# RGBW_DirectControl_Eagle740.net
KiCad netlist of a schematic drawn in EAGLE
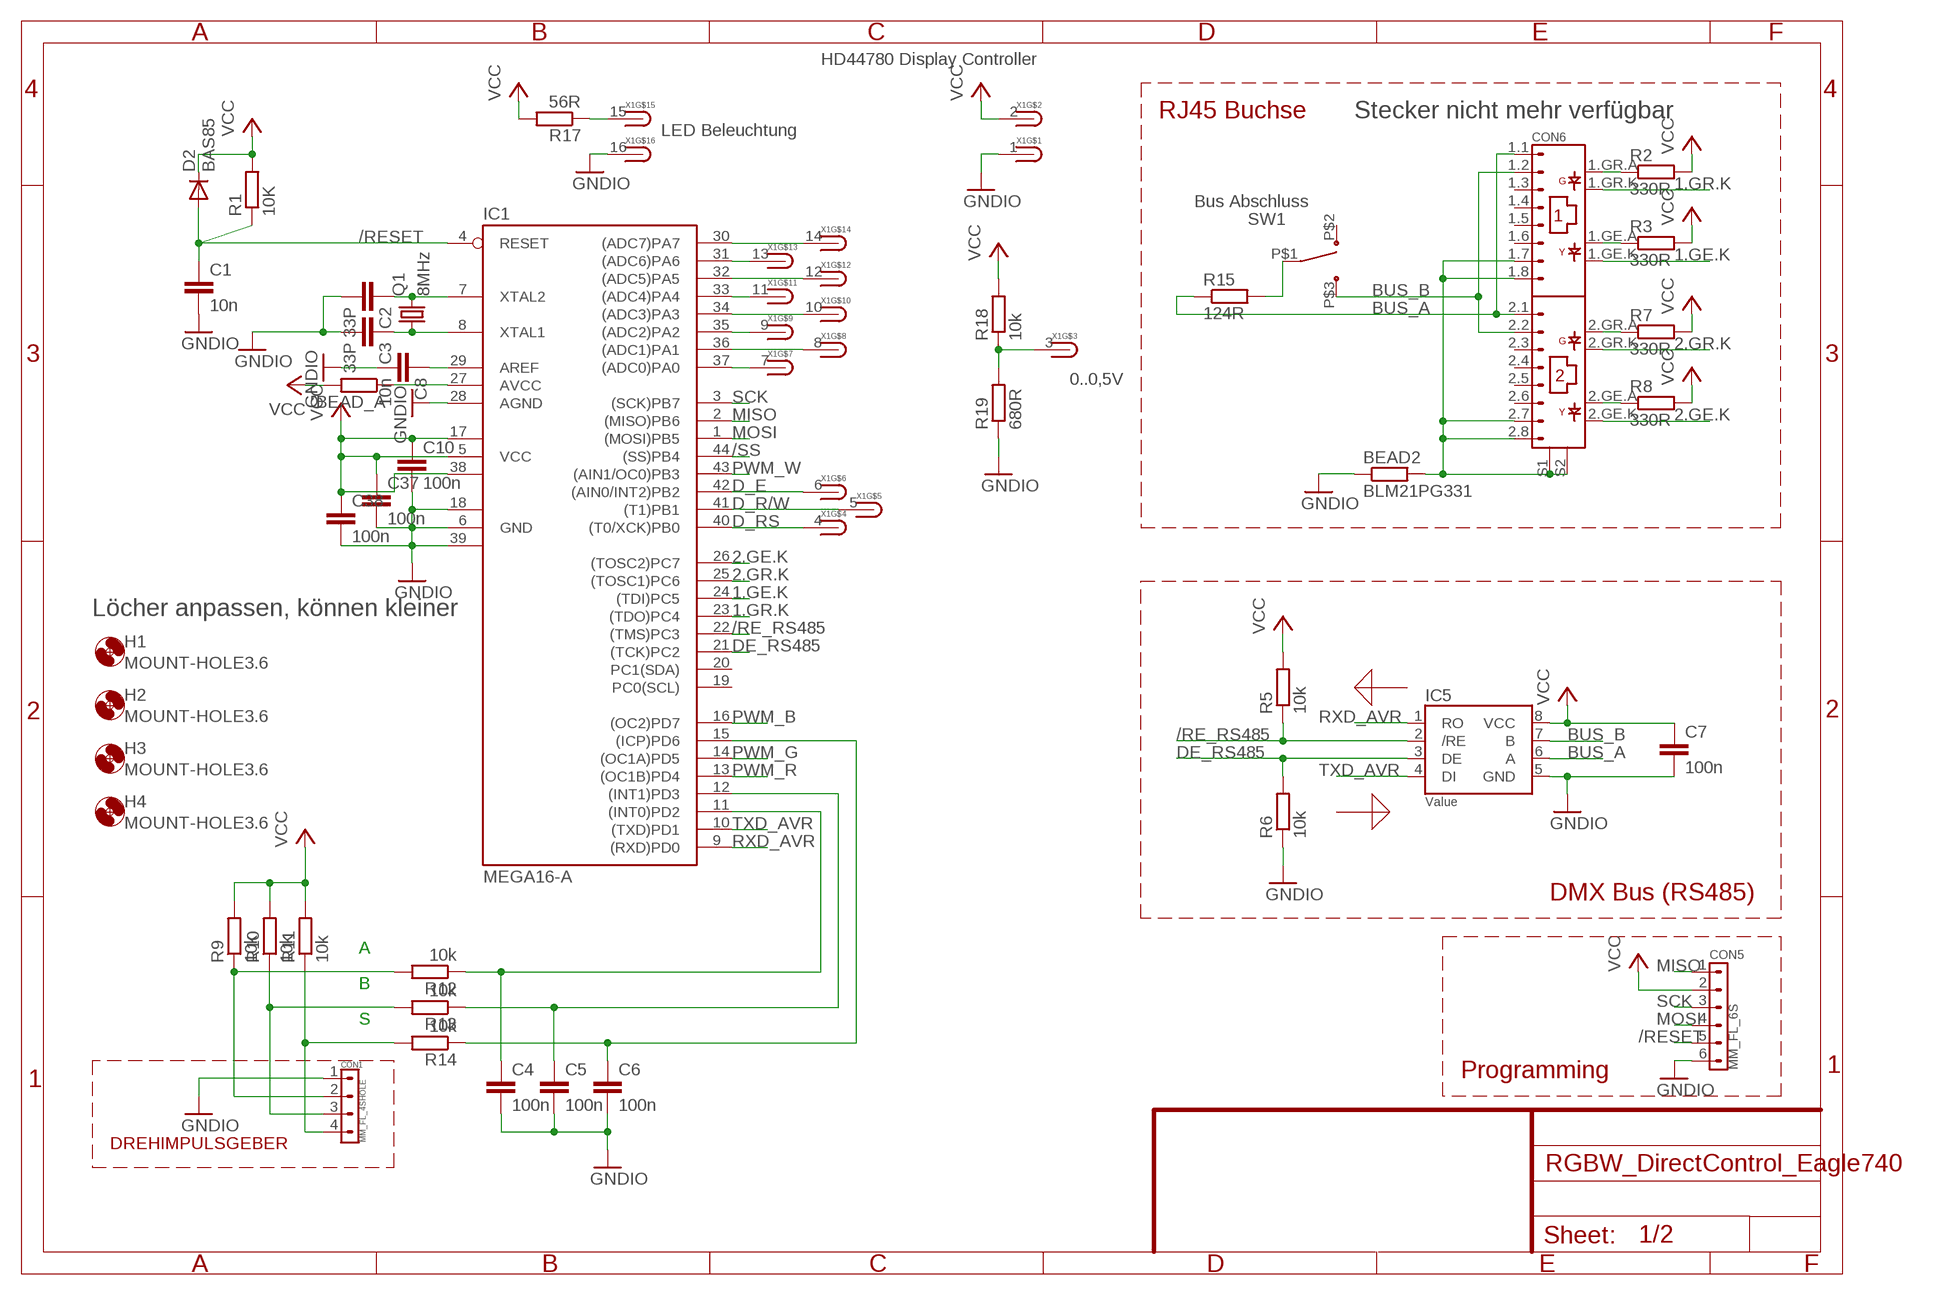
[diagram p0: schematic, sheet 1]
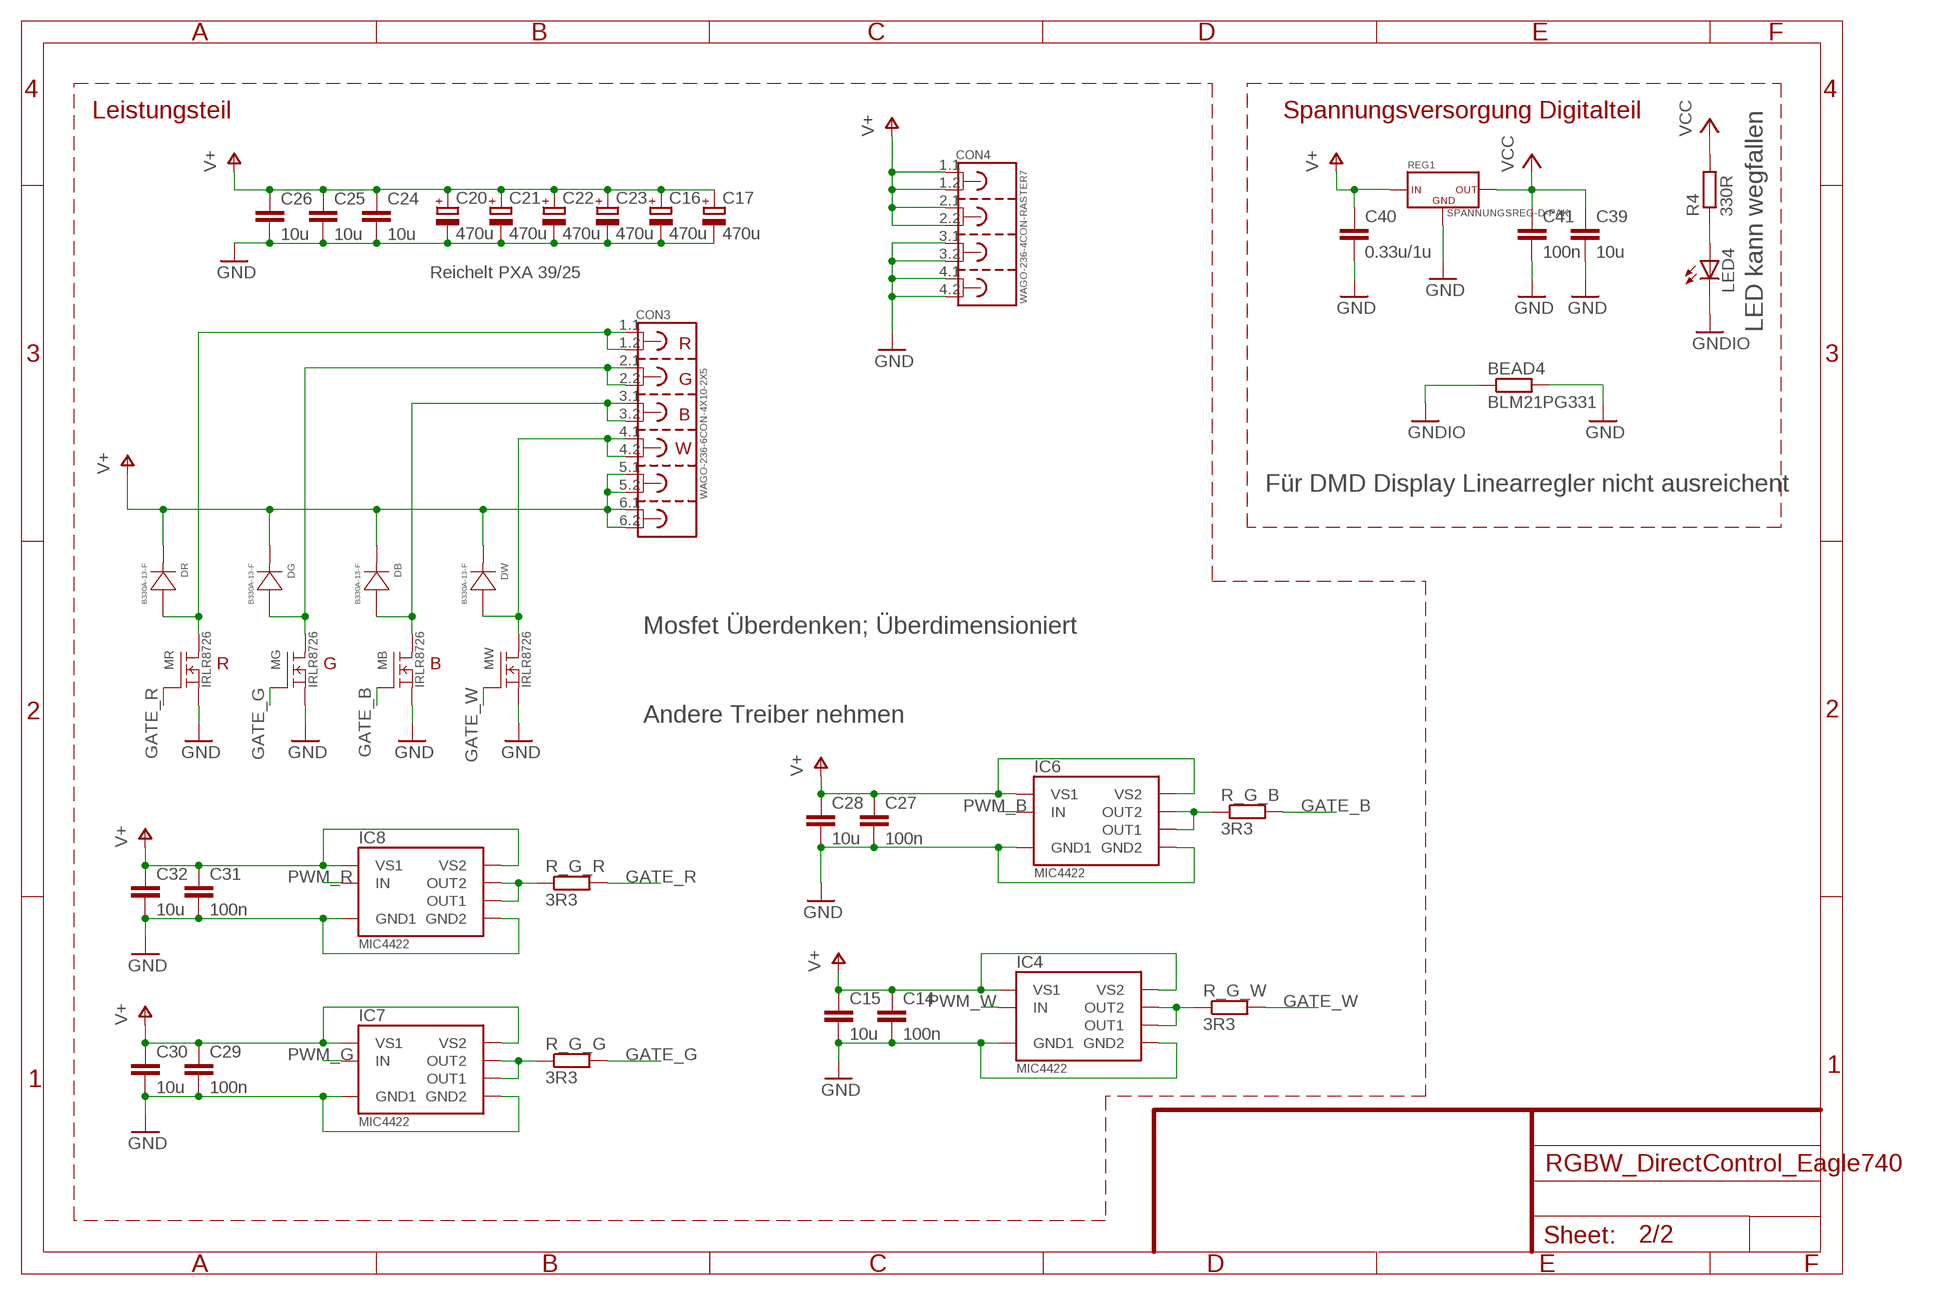
[diagram p1: schematic, sheet 2]

(export (version "E")
  (design (tool "Eeschema 10.0.6"))
  (components
    (comp (ref "BEAD2")
      (value "BLM21PG331")
      (footprint "eagle-import:R0805")
      (libsource (lib "eagle-import") (part "R-EU_R0805"))
    )
    (comp (ref "BEAD_A")
      (value "R-EU_R0805")
      (footprint "eagle-import:R0805")
      (libsource (lib "eagle-import") (part "R-EU_R0805"))
    )
    (comp (ref "C1")
      (value "10n")
      (footprint "eagle-import:C0805")
      (libsource (lib "eagle-import") (part "C-EUC0805"))
    )
    (comp (ref "C2")
      (value "33P")
      (footprint "eagle-import:C0805")
      (libsource (lib "eagle-import") (part "C-EUC0805"))
    )
    (comp (ref "C3")
      (value "33P")
      (footprint "eagle-import:C0805")
      (libsource (lib "eagle-import") (part "C-EUC0805"))
    )
    (comp (ref "C4")
      (value "100n")
      (footprint "eagle-import:C0805")
      (libsource (lib "eagle-import") (part "C-EUC0805"))
    )
    (comp (ref "C5")
      (value "100n")
      (footprint "eagle-import:C0805")
      (libsource (lib "eagle-import") (part "C-EUC0805"))
    )
    (comp (ref "C6")
      (value "100n")
      (footprint "eagle-import:C0805")
      (libsource (lib "eagle-import") (part "C-EUC0805"))
    )
    (comp (ref "C7")
      (value "100n")
      (footprint "eagle-import:C0805")
      (libsource (lib "eagle-import") (part "C-EUC0805"))
    )
    (comp (ref "C8")
      (value "10n")
      (footprint "eagle-import:C0805")
      (libsource (lib "eagle-import") (part "C-EUC0805"))
    )
    (comp (ref "C10")
      (value "100n")
      (footprint "eagle-import:C0805")
      (libsource (lib "eagle-import") (part "C-EUC0805"))
    )
    (comp (ref "C37")
      (value "100n")
      (footprint "eagle-import:C0805")
      (libsource (lib "eagle-import") (part "C-EUC0805"))
    )
    (comp (ref "C38")
      (value "100n")
      (footprint "eagle-import:C0805")
      (libsource (lib "eagle-import") (part "C-EUC0805"))
    )
    (comp (ref "CON1")
      (value "MM_FL_4SHOLE")
      (footprint "eagle-import:MM_FL_4G")
      (libsource (lib "eagle-import") (part "MM_FL_4SHOLE"))
    )
    (comp (ref "CON5")
      (value "MM_FL_6S")
      (footprint "eagle-import:MM_FL_6G")
      (libsource (lib "eagle-import") (part "MM_FL_6STH"))
    )
    (comp (ref "CON6")
      (value "RJ45_2ER_LED")
      (footprint "eagle-import:RJ45_2ER_LED")
      (libsource (lib "eagle-import") (part "RJ45_2ER_LED"))
    )
    (comp (ref "D2")
      (value "BAS85")
      (footprint "eagle-import:SOD80C")
      (libsource (lib "eagle-import") (part "DIODE-SOD80C"))
    )
    (comp (ref "H1")
      (value "MOUNT-HOLE3.6")
      (footprint "eagle-import:3,6")
      (libsource (lib "eagle-import") (part "MOUNT-HOLE3.6"))
    )
    (comp (ref "H2")
      (value "MOUNT-HOLE3.6")
      (footprint "eagle-import:3,6")
      (libsource (lib "eagle-import") (part "MOUNT-HOLE3.6"))
    )
    (comp (ref "H3")
      (value "MOUNT-HOLE3.6")
      (footprint "eagle-import:3,6")
      (libsource (lib "eagle-import") (part "MOUNT-HOLE3.6"))
    )
    (comp (ref "H4")
      (value "MOUNT-HOLE3.6")
      (footprint "eagle-import:3,6")
      (libsource (lib "eagle-import") (part "MOUNT-HOLE3.6"))
    )
    (comp (ref "IC1")
      (value "MEGA16-A")
      (footprint "eagle-import:TQFP44")
      (libsource (lib "eagle-import") (part "MEGA16-A"))
    )
    (comp (ref "IC5")
      (value "LT1785")
      (footprint "eagle-import:SO08")
      (libsource (lib "eagle-import") (part "LT1785"))
    )
    (comp (ref "Q1")
      (value "8MHz")
      (footprint "eagle-import:HC49_S")
      (libsource (lib "eagle-import") (part "CRYTALHC49S"))
    )
    (comp (ref "R1")
      (value "10K")
      (footprint "eagle-import:R0805")
      (libsource (lib "eagle-import") (part "R-EU_R0805"))
    )
    (comp (ref "R2")
      (value "330R")
      (footprint "eagle-import:R0805")
      (libsource (lib "eagle-import") (part "R-EU_R0805"))
    )
    (comp (ref "R3")
      (value "330R")
      (footprint "eagle-import:R0805")
      (libsource (lib "eagle-import") (part "R-EU_R0805"))
    )
    (comp (ref "R5")
      (value "10k")
      (footprint "eagle-import:R0805")
      (libsource (lib "eagle-import") (part "R-EU_R0805"))
    )
    (comp (ref "R6")
      (value "10k")
      (footprint "eagle-import:R0805")
      (libsource (lib "eagle-import") (part "R-EU_R0805"))
    )
    (comp (ref "R7")
      (value "330R")
      (footprint "eagle-import:R0805")
      (libsource (lib "eagle-import") (part "R-EU_R0805"))
    )
    (comp (ref "R8")
      (value "330R")
      (footprint "eagle-import:R0805")
      (libsource (lib "eagle-import") (part "R-EU_R0805"))
    )
    (comp (ref "R9")
      (value "10k")
      (footprint "eagle-import:R0603")
      (libsource (lib "eagle-import") (part "R-EU_R0603"))
    )
    (comp (ref "R10")
      (value "10k")
      (footprint "eagle-import:R0603")
      (libsource (lib "eagle-import") (part "R-EU_R0603"))
    )
    (comp (ref "R11")
      (value "10k")
      (footprint "eagle-import:R0603")
      (libsource (lib "eagle-import") (part "R-EU_R0603"))
    )
    (comp (ref "R12")
      (value "10k")
      (footprint "eagle-import:R0603")
      (libsource (lib "eagle-import") (part "R-EU_R0603"))
    )
    (comp (ref "R13")
      (value "10k")
      (footprint "eagle-import:R0603")
      (libsource (lib "eagle-import") (part "R-EU_R0603"))
    )
    (comp (ref "R14")
      (value "10k")
      (footprint "eagle-import:R0603")
      (libsource (lib "eagle-import") (part "R-EU_R0603"))
    )
    (comp (ref "R15")
      (value "124R")
      (footprint "eagle-import:R0805")
      (libsource (lib "eagle-import") (part "R-EU_R0805"))
    )
    (comp (ref "R17")
      (value "56R")
      (footprint "eagle-import:R0805")
      (libsource (lib "eagle-import") (part "R-EU_R0805"))
    )
    (comp (ref "R18")
      (value "10k")
      (footprint "eagle-import:R0603")
      (libsource (lib "eagle-import") (part "R-EU_R0603"))
    )
    (comp (ref "R19")
      (value "680R")
      (footprint "eagle-import:R0603")
      (libsource (lib "eagle-import") (part "R-EU_R0603"))
    )
    (comp (ref "SW1")
      (value "SWITCH_NK236")
      (footprint "eagle-import:SWITCH_NK236")
      (libsource (lib "eagle-import") (part "SWITCH_NK236"))
    )
    (comp (ref "X1")
      (value "MM_FL_16GTH")
      (footprint "eagle-import:MM_FL16G")
      (libsource (lib "eagle-import") (part "MM_FL_16GTH"))
    )
    (comp (ref "BEAD4")
      (value "BLM21PG331")
      (footprint "eagle-import:R0805")
      (libsource (lib "eagle-import") (part "R-EU_R0805"))
    )
    (comp (ref "C14")
      (value "100n")
      (footprint "eagle-import:C0805")
      (libsource (lib "eagle-import") (part "C-EUC0805"))
    )
    (comp (ref "C15")
      (value "10u")
      (footprint "eagle-import:C0805")
      (libsource (lib "eagle-import") (part "C-EUC0805"))
    )
    (comp (ref "C16")
      (value "470u")
      (footprint "eagle-import:E5-10,5")
      (libsource (lib "eagle-import") (part "CPOL-EUE5-10.5"))
    )
    (comp (ref "C17")
      (value "470u")
      (footprint "eagle-import:E5-10,5")
      (libsource (lib "eagle-import") (part "CPOL-EUE5-10.5"))
    )
    (comp (ref "C20")
      (value "470u")
      (footprint "eagle-import:E5-10,5")
      (libsource (lib "eagle-import") (part "CPOL-EUE5-10.5"))
    )
    (comp (ref "C21")
      (value "470u")
      (footprint "eagle-import:E5-10,5")
      (libsource (lib "eagle-import") (part "CPOL-EUE5-10.5"))
    )
    (comp (ref "C22")
      (value "470u")
      (footprint "eagle-import:E5-10,5")
      (libsource (lib "eagle-import") (part "CPOL-EUE5-10.5"))
    )
    (comp (ref "C23")
      (value "470u")
      (footprint "eagle-import:E5-10,5")
      (libsource (lib "eagle-import") (part "CPOL-EUE5-10.5"))
    )
    (comp (ref "C24")
      (value "10u")
      (footprint "eagle-import:C0805")
      (libsource (lib "eagle-import") (part "C-EUC0805"))
    )
    (comp (ref "C25")
      (value "10u")
      (footprint "eagle-import:C0805")
      (libsource (lib "eagle-import") (part "C-EUC0805"))
    )
    (comp (ref "C26")
      (value "10u")
      (footprint "eagle-import:C0805")
      (libsource (lib "eagle-import") (part "C-EUC0805"))
    )
    (comp (ref "C27")
      (value "100n")
      (footprint "eagle-import:C0805")
      (libsource (lib "eagle-import") (part "C-EUC0805"))
    )
    (comp (ref "C28")
      (value "10u")
      (footprint "eagle-import:C0805")
      (libsource (lib "eagle-import") (part "C-EUC0805"))
    )
    (comp (ref "C29")
      (value "100n")
      (footprint "eagle-import:C0805")
      (libsource (lib "eagle-import") (part "C-EUC0805"))
    )
    (comp (ref "C30")
      (value "10u")
      (footprint "eagle-import:C0805")
      (libsource (lib "eagle-import") (part "C-EUC0805"))
    )
    (comp (ref "C31")
      (value "100n")
      (footprint "eagle-import:C0805")
      (libsource (lib "eagle-import") (part "C-EUC0805"))
    )
    (comp (ref "C32")
      (value "10u")
      (footprint "eagle-import:C0805")
      (libsource (lib "eagle-import") (part "C-EUC0805"))
    )
    (comp (ref "C39")
      (value "10u")
      (footprint "eagle-import:C0805")
      (libsource (lib "eagle-import") (part "C-EUC0805"))
    )
    (comp (ref "C40")
      (value "0.33u/1u")
      (footprint "eagle-import:C0805")
      (libsource (lib "eagle-import") (part "C-EUC0805"))
    )
    (comp (ref "C41")
      (value "100n")
      (footprint "eagle-import:C0805")
      (libsource (lib "eagle-import") (part "C-EUC0805"))
    )
    (comp (ref "CON3")
      (value "WAGO-236-6CON-4X10-2X5")
      (footprint "eagle-import:WAGO236_2X5_4X10")
      (libsource (lib "eagle-import") (part "WAGO-236-6CON-4X10-2X5"))
    )
    (comp (ref "CON4")
      (value "WAGO-236-4CON-RASTER7")
      (footprint "eagle-import:WAGO236_7.5_4")
      (libsource (lib "eagle-import") (part "WAGO-236-4CON-RASTER7"))
    )
    (comp (ref "DB")
      (value "B330A-13-F")
      (footprint "eagle-import:SMA")
      (libsource (lib "eagle-import") (part "B330A-13-F"))
    )
    (comp (ref "DG")
      (value "B330A-13-F")
      (footprint "eagle-import:SMA")
      (libsource (lib "eagle-import") (part "B330A-13-F"))
    )
    (comp (ref "DR")
      (value "B330A-13-F")
      (footprint "eagle-import:SMA")
      (libsource (lib "eagle-import") (part "B330A-13-F"))
    )
    (comp (ref "DW")
      (value "B330A-13-F")
      (footprint "eagle-import:SMA")
      (libsource (lib "eagle-import") (part "B330A-13-F"))
    )
    (comp (ref "IC4")
      (value "MIC4422")
      (footprint "eagle-import:SO08")
      (libsource (lib "eagle-import") (part "MIC4422"))
    )
    (comp (ref "IC6")
      (value "MIC4422")
      (footprint "eagle-import:SO08")
      (libsource (lib "eagle-import") (part "MIC4422"))
    )
    (comp (ref "IC7")
      (value "MIC4422")
      (footprint "eagle-import:SO08")
      (libsource (lib "eagle-import") (part "MIC4422"))
    )
    (comp (ref "IC8")
      (value "MIC4422")
      (footprint "eagle-import:SO08")
      (libsource (lib "eagle-import") (part "MIC4422"))
    )
    (comp (ref "LED4")
      (value "LEDCHIP-LED0805")
      (footprint "eagle-import:CHIP-LED0805")
      (libsource (lib "eagle-import") (part "LEDCHIP-LED0805"))
    )
    (comp (ref "MB")
      (value "IRLR8726")
      (footprint "eagle-import:D-PAK")
      (libsource (lib "eagle-import") (part "IRLR8726"))
    )
    (comp (ref "MG")
      (value "IRLR8726")
      (footprint "eagle-import:D-PAK")
      (libsource (lib "eagle-import") (part "IRLR8726"))
    )
    (comp (ref "MR")
      (value "IRLR8726")
      (footprint "eagle-import:D-PAK")
      (libsource (lib "eagle-import") (part "IRLR8726"))
    )
    (comp (ref "MW")
      (value "IRLR8726")
      (footprint "eagle-import:D-PAK")
      (libsource (lib "eagle-import") (part "IRLR8726"))
    )
    (comp (ref "R4")
      (value "330R")
      (footprint "eagle-import:R0805")
      (libsource (lib "eagle-import") (part "R-EU_R0805"))
    )
    (comp (ref "REG1")
      (value "SPANNUNGSREG-D-PAK")
      (footprint "eagle-import:D-PAK")
      (libsource (lib "eagle-import") (part "SPANNUNGSREG-D-PAK"))
    )
    (comp (ref "R_G_B")
      (value "3R3")
      (footprint "eagle-import:R0805")
      (libsource (lib "eagle-import") (part "R-EU_R0805"))
    )
    (comp (ref "R_G_G")
      (value "3R3")
      (footprint "eagle-import:R0805")
      (libsource (lib "eagle-import") (part "R-EU_R0805"))
    )
    (comp (ref "R_G_R")
      (value "3R3")
      (footprint "eagle-import:R0805")
      (libsource (lib "eagle-import") (part "R-EU_R0805"))
    )
    (comp (ref "R_G_W")
      (value "3R3")
      (footprint "eagle-import:R0805")
      (libsource (lib "eagle-import") (part "R-EU_R0805"))
    )
  )
  (nets
    (net (code "1") (name "1.GE.K") (class "Default")
      (node (ref "CON6") (pin "1.GE.K") (pinfunction "1.GE.K_1.GE.K") (pintype "bidirectional"))
      (node (ref "IC1") (pin "24") (pinfunction "(TDI)PC5_24") (pintype "bidirectional"))
    )
    (net (code "2") (name "1.GR.K") (class "Default")
      (node (ref "CON6") (pin "1.GR.K") (pinfunction "1.GR.K_1.GR.K") (pintype "bidirectional"))
      (node (ref "IC1") (pin "23") (pinfunction "(TDO)PC4_23") (pintype "bidirectional"))
    )
    (net (code "3") (name "2.GE.K") (class "Default")
      (node (ref "CON6") (pin "2.GE.K") (pinfunction "2.GE.K_2.GE.K") (pintype "bidirectional"))
      (node (ref "IC1") (pin "26") (pinfunction "(TOSC2)PC7_26") (pintype "bidirectional"))
    )
    (net (code "4") (name "2.GR.K") (class "Default")
      (node (ref "CON6") (pin "2.GR.K") (pinfunction "2.GR.K_2.GR.K") (pintype "bidirectional"))
      (node (ref "IC1") (pin "25") (pinfunction "(TOSC1)PC6_25") (pintype "bidirectional"))
    )
    (net (code "5") (name "BUS_A") (class "Default")
      (node (ref "CON6") (pin "1.1") (pinfunction "1.1_1.1") (pintype "bidirectional"))
      (node (ref "CON6") (pin "2.1") (pinfunction "2.1_2.1") (pintype "bidirectional"))
      (node (ref "IC5") (pin "6") (pinfunction "A_6") (pintype "bidirectional"))
      (node (ref "R15") (pin "1") (pinfunction "1_1") (pintype "passive"))
    )
    (net (code "6") (name "BUS_B") (class "Default")
      (node (ref "CON6") (pin "1.2") (pinfunction "1.2_1.2") (pintype "bidirectional"))
      (node (ref "CON6") (pin "2.2") (pinfunction "2.2_2.2") (pintype "bidirectional"))
      (node (ref "IC5") (pin "7") (pinfunction "B_7") (pintype "bidirectional"))
      (node (ref "SW1") (pin "P$3") (pinfunction "3_P$3") (pintype "bidirectional"))
    )
    (net (code "7") (name "DE_RS485") (class "Default")
      (node (ref "IC1") (pin "21") (pinfunction "(TCK)PC2_21") (pintype "bidirectional"))
      (node (ref "IC5") (pin "3") (pinfunction "DE_3") (pintype "bidirectional"))
      (node (ref "R6") (pin "2") (pinfunction "2_2") (pintype "passive"))
    )
    (net (code "8") (name "D_E") (class "Default")
      (node (ref "IC1") (pin "42") (pinfunction "(AIN0/INT2)PB2_42") (pintype "bidirectional"))
      (node (ref "X1") (pin "6") (pinfunction "P$1_6") (pintype "bidirectional"))
    )
    (net (code "9") (name "D_RS") (class "Default")
      (node (ref "IC1") (pin "40") (pinfunction "(T0/XCK)PB0_40") (pintype "bidirectional"))
      (node (ref "X1") (pin "4") (pinfunction "P$1_4") (pintype "bidirectional"))
    )
    (net (code "10") (name "D_R{slash}W") (class "Default")
      (node (ref "IC1") (pin "41") (pinfunction "(T1)PB1_41") (pintype "bidirectional"))
      (node (ref "X1") (pin "5") (pinfunction "P$1_5") (pintype "bidirectional"))
    )
    (net (code "11") (name "GATE_B") (class "Default")
      (node (ref "MB") (pin "G") (pinfunction "G_G") (pintype "bidirectional"))
      (node (ref "R_G_B") (pin "2") (pinfunction "2_2") (pintype "passive"))
    )
    (net (code "12") (name "GATE_G") (class "Default")
      (node (ref "MG") (pin "G") (pinfunction "G_G") (pintype "bidirectional"))
      (node (ref "R_G_G") (pin "2") (pinfunction "2_2") (pintype "passive"))
    )
    (net (code "13") (name "GATE_R") (class "Default")
      (node (ref "MR") (pin "G") (pinfunction "G_G") (pintype "bidirectional"))
      (node (ref "R_G_R") (pin "2") (pinfunction "2_2") (pintype "passive"))
    )
    (net (code "14") (name "GATE_W") (class "Default")
      (node (ref "MW") (pin "G") (pinfunction "G_G") (pintype "bidirectional"))
      (node (ref "R_G_W") (pin "2") (pinfunction "2_2") (pintype "passive"))
    )
    (net (code "15") (name "GND") (class "Default")
      (node (ref "BEAD4") (pin "2") (pinfunction "2_2") (pintype "passive"))
      (node (ref "C14") (pin "2") (pinfunction "2_2") (pintype "passive"))
      (node (ref "C15") (pin "2") (pinfunction "2_2") (pintype "passive"))
      (node (ref "C16") (pin "-") (pinfunction "-_-") (pintype "passive"))
      (node (ref "C17") (pin "-") (pinfunction "-_-") (pintype "passive"))
      (node (ref "C20") (pin "-") (pinfunction "-_-") (pintype "passive"))
      (node (ref "C21") (pin "-") (pinfunction "-_-") (pintype "passive"))
      (node (ref "C22") (pin "-") (pinfunction "-_-") (pintype "passive"))
      (node (ref "C23") (pin "-") (pinfunction "-_-") (pintype "passive"))
      (node (ref "C24") (pin "2") (pinfunction "2_2") (pintype "passive"))
      (node (ref "C25") (pin "2") (pinfunction "2_2") (pintype "passive"))
      (node (ref "C26") (pin "2") (pinfunction "2_2") (pintype "passive"))
      (node (ref "C27") (pin "2") (pinfunction "2_2") (pintype "passive"))
      (node (ref "C28") (pin "2") (pinfunction "2_2") (pintype "passive"))
      (node (ref "C29") (pin "2") (pinfunction "2_2") (pintype "passive"))
      (node (ref "C30") (pin "2") (pinfunction "2_2") (pintype "passive"))
      (node (ref "C31") (pin "2") (pinfunction "2_2") (pintype "passive"))
      (node (ref "C32") (pin "2") (pinfunction "2_2") (pintype "passive"))
      (node (ref "C39") (pin "2") (pinfunction "2_2") (pintype "passive"))
      (node (ref "C40") (pin "2") (pinfunction "2_2") (pintype "passive"))
      (node (ref "C41") (pin "2") (pinfunction "2_2") (pintype "passive"))
      (node (ref "CON4") (pin "3.1") (pinfunction "P$5_3.1") (pintype "bidirectional"))
      (node (ref "CON4") (pin "3.2") (pinfunction "P$6_3.2") (pintype "bidirectional"))
      (node (ref "CON4") (pin "4.1") (pinfunction "P$7_4.1") (pintype "bidirectional"))
      (node (ref "CON4") (pin "4.2") (pinfunction "P$8_4.2") (pintype "bidirectional"))
      (node (ref "IC4") (pin "4") (pinfunction "GND1_4") (pintype "bidirectional"))
      (node (ref "IC4") (pin "5") (pinfunction "GND2_5") (pintype "bidirectional"))
      (node (ref "IC6") (pin "4") (pinfunction "GND1_4") (pintype "bidirectional"))
      (node (ref "IC6") (pin "5") (pinfunction "GND2_5") (pintype "bidirectional"))
      (node (ref "IC7") (pin "4") (pinfunction "GND1_4") (pintype "bidirectional"))
      (node (ref "IC7") (pin "5") (pinfunction "GND2_5") (pintype "bidirectional"))
      (node (ref "IC8") (pin "4") (pinfunction "GND1_4") (pintype "bidirectional"))
      (node (ref "IC8") (pin "5") (pinfunction "GND2_5") (pintype "bidirectional"))
      (node (ref "MB") (pin "S") (pinfunction "S_S") (pintype "bidirectional"))
      (node (ref "MG") (pin "S") (pinfunction "S_S") (pintype "bidirectional"))
      (node (ref "MR") (pin "S") (pinfunction "S_S") (pintype "bidirectional"))
      (node (ref "MW") (pin "S") (pinfunction "S_S") (pintype "bidirectional"))
      (node (ref "REG1") (pin "D") (pinfunction "GND_D") (pintype "bidirectional"))
    )
    (net (code "16") (name "GNDIO") (class "Default")
      (node (ref "BEAD2") (pin "1") (pinfunction "1_1") (pintype "passive"))
      (node (ref "BEAD4") (pin "1") (pinfunction "1_1") (pintype "passive"))
      (node (ref "C1") (pin "2") (pinfunction "2_2") (pintype "passive"))
      (node (ref "C10") (pin "2") (pinfunction "2_2") (pintype "passive"))
      (node (ref "C2") (pin "2") (pinfunction "2_2") (pintype "passive"))
      (node (ref "C3") (pin "2") (pinfunction "2_2") (pintype "passive"))
      (node (ref "C37") (pin "2") (pinfunction "2_2") (pintype "passive"))
      (node (ref "C38") (pin "2") (pinfunction "2_2") (pintype "passive"))
      (node (ref "C4") (pin "2") (pinfunction "2_2") (pintype "passive"))
      (node (ref "C5") (pin "2") (pinfunction "2_2") (pintype "passive"))
      (node (ref "C6") (pin "2") (pinfunction "2_2") (pintype "passive"))
      (node (ref "C7") (pin "2") (pinfunction "2_2") (pintype "passive"))
      (node (ref "C8") (pin "2") (pinfunction "2_2") (pintype "passive"))
      (node (ref "CON1") (pin "1") (pinfunction "P$1_1") (pintype "bidirectional"))
      (node (ref "CON5") (pin "6") (pinfunction "P$6_6") (pintype "bidirectional"))
      (node (ref "IC1") (pin "18") (pinfunction "GND1_18") (pintype "power_in"))
      (node (ref "IC1") (pin "28") (pinfunction "AGND_28") (pintype "power_in"))
      (node (ref "IC1") (pin "39") (pinfunction "GND2_39") (pintype "power_in"))
      (node (ref "IC1") (pin "6") (pinfunction "GND_6") (pintype "power_in"))
      (node (ref "IC5") (pin "5") (pinfunction "GND_5") (pintype "bidirectional"))
      (node (ref "LED4") (pin "C") (pinfunction "C_C") (pintype "passive"))
      (node (ref "R19") (pin "1") (pinfunction "1_1") (pintype "passive"))
      (node (ref "R6") (pin "1") (pinfunction "1_1") (pintype "passive"))
      (node (ref "X1") (pin "1") (pinfunction "P$1_1") (pintype "bidirectional"))
      (node (ref "X1") (pin "16") (pinfunction "P$1_16") (pintype "bidirectional"))
    )
    (net (code "17") (name "MISO") (class "Default")
      (node (ref "CON5") (pin "1") (pinfunction "P$1_1") (pintype "bidirectional"))
      (node (ref "IC1") (pin "2") (pinfunction "(MISO)PB6_2") (pintype "bidirectional"))
    )
    (net (code "18") (name "MOSI") (class "Default")
      (node (ref "CON5") (pin "4") (pinfunction "P$4_4") (pintype "bidirectional"))
      (node (ref "IC1") (pin "1") (pinfunction "(MOSI)PB5_1") (pintype "bidirectional"))
    )
    (net (code "19") (name "Net-(BEAD2-Pad2)") (class "Default")
      (node (ref "BEAD2") (pin "2") (pinfunction "2_2") (pintype "passive"))
      (node (ref "CON6") (pin "1.7") (pinfunction "1.7_1.7") (pintype "bidirectional"))
      (node (ref "CON6") (pin "1.8") (pinfunction "1.8_1.8") (pintype "bidirectional"))
      (node (ref "CON6") (pin "2.7") (pinfunction "2.7_2.7") (pintype "bidirectional"))
      (node (ref "CON6") (pin "2.8") (pinfunction "2.8_2.8") (pintype "bidirectional"))
      (node (ref "CON6") (pin "S1") (pinfunction "S1_S1") (pintype "bidirectional"))
      (node (ref "CON6") (pin "S2") (pinfunction "S2_S2") (pintype "bidirectional"))
    )
    (net (code "20") (name "Net-(CON1-P$2)") (class "Default")
      (node (ref "CON1") (pin "2") (pinfunction "P$2_2") (pintype "bidirectional"))
      (node (ref "R12") (pin "2") (pinfunction "2_2") (pintype "passive"))
      (node (ref "R9") (pin "1") (pinfunction "1_1") (pintype "passive"))
    )
    (net (code "21") (name "Net-(CON1-P$3)") (class "Default")
      (node (ref "CON1") (pin "3") (pinfunction "P$3_3") (pintype "bidirectional"))
      (node (ref "R10") (pin "1") (pinfunction "1_1") (pintype "passive"))
      (node (ref "R13") (pin "2") (pinfunction "2_2") (pintype "passive"))
    )
    (net (code "22") (name "Net-(CON1-P$4)") (class "Default")
      (node (ref "CON1") (pin "4") (pinfunction "P$4_4") (pintype "bidirectional"))
      (node (ref "R11") (pin "1") (pinfunction "1_1") (pintype "passive"))
      (node (ref "R14") (pin "2") (pinfunction "2_2") (pintype "passive"))
    )
    (net (code "23") (name "Net-(CON3-3.3)") (class "Default")
      (node (ref "CON3") (pin "3.1") (pinfunction "3.1_3.1") (pintype "bidirectional"))
      (node (ref "CON3") (pin "3.2") (pinfunction "3.3_3.2") (pintype "bidirectional"))
      (node (ref "DB") (pin "A") (pinfunction "A_A") (pintype "bidirectional"))
      (node (ref "MB") (pin "D") (pinfunction "D_D") (pintype "bidirectional"))
    )
    (net (code "24") (name "Net-(CON3-Pad1.1)") (class "Default")
      (node (ref "CON3") (pin "1.1") (pinfunction "1.1_1.1") (pintype "bidirectional"))
      (node (ref "CON3") (pin "1.2") (pinfunction "1.2_1.2") (pintype "bidirectional"))
      (node (ref "DR") (pin "A") (pinfunction "A_A") (pintype "bidirectional"))
      (node (ref "MR") (pin "D") (pinfunction "D_D") (pintype "bidirectional"))
    )
    (net (code "25") (name "Net-(CON3-Pad2.1)") (class "Default")
      (node (ref "CON3") (pin "2.1") (pinfunction "2.1_2.1") (pintype "bidirectional"))
      (node (ref "CON3") (pin "2.2") (pinfunction "2.2_2.2") (pintype "bidirectional"))
      (node (ref "DG") (pin "A") (pinfunction "A_A") (pintype "bidirectional"))
      (node (ref "MG") (pin "D") (pinfunction "D_D") (pintype "bidirectional"))
    )
    (net (code "26") (name "Net-(CON3-Pad4.1)") (class "Default")
      (node (ref "CON3") (pin "4.1") (pinfunction "4.1_4.1") (pintype "bidirectional"))
      (node (ref "CON3") (pin "4.2") (pinfunction "4.2_4.2") (pintype "bidirectional"))
      (node (ref "DW") (pin "A") (pinfunction "A_A") (pintype "bidirectional"))
      (node (ref "MW") (pin "D") (pinfunction "D_D") (pintype "bidirectional"))
    )
    (net (code "27") (name "Net-(CON6-Pad1.GE.A)") (class "Default")
      (node (ref "CON6") (pin "1.GE.A") (pinfunction "1.GE.A_1.GE.A") (pintype "bidirectional"))
      (node (ref "R3") (pin "1") (pinfunction "1_1") (pintype "passive"))
    )
    (net (code "28") (name "Net-(CON6-Pad1.GR.A)") (class "Default")
      (node (ref "CON6") (pin "1.GR.A") (pinfunction "1.GR.A_1.GR.A") (pintype "bidirectional"))
      (node (ref "R2") (pin "1") (pinfunction "1_1") (pintype "passive"))
    )
    (net (code "29") (name "Net-(CON6-Pad2.GE.A)") (class "Default")
      (node (ref "CON6") (pin "2.GE.A") (pinfunction "2.GE.A_2.GE.A") (pintype "bidirectional"))
      (node (ref "R8") (pin "1") (pinfunction "1_1") (pintype "passive"))
    )
    (net (code "30") (name "Net-(CON6-Pad2.GR.A)") (class "Default")
      (node (ref "CON6") (pin "2.GR.A") (pinfunction "2.GR.A_2.GR.A") (pintype "bidirectional"))
      (node (ref "R7") (pin "1") (pinfunction "1_1") (pintype "passive"))
    )
    (net (code "31") (name "Net-(IC1-(ADC0)PA0)") (class "Default")
      (node (ref "IC1") (pin "37") (pinfunction "(ADC0)PA0_37") (pintype "bidirectional"))
      (node (ref "X1") (pin "7") (pinfunction "P$1_7") (pintype "bidirectional"))
    )
    (net (code "32") (name "Net-(IC1-(ADC1)PA1)") (class "Default")
      (node (ref "IC1") (pin "36") (pinfunction "(ADC1)PA1_36") (pintype "bidirectional"))
      (node (ref "X1") (pin "8") (pinfunction "P$1_8") (pintype "bidirectional"))
    )
    (net (code "33") (name "Net-(IC1-(ADC2)PA2)") (class "Default")
      (node (ref "IC1") (pin "35") (pinfunction "(ADC2)PA2_35") (pintype "bidirectional"))
      (node (ref "X1") (pin "9") (pinfunction "P$1_9") (pintype "bidirectional"))
    )
    (net (code "34") (name "Net-(IC1-(ADC3)PA3)") (class "Default")
      (node (ref "IC1") (pin "34") (pinfunction "(ADC3)PA3_34") (pintype "bidirectional"))
      (node (ref "X1") (pin "10") (pinfunction "P$1_10") (pintype "bidirectional"))
    )
    (net (code "35") (name "Net-(IC1-(ADC4)PA4)") (class "Default")
      (node (ref "IC1") (pin "33") (pinfunction "(ADC4)PA4_33") (pintype "bidirectional"))
      (node (ref "X1") (pin "11") (pinfunction "P$1_11") (pintype "bidirectional"))
    )
    (net (code "36") (name "Net-(IC1-(ADC5)PA5)") (class "Default")
      (node (ref "IC1") (pin "32") (pinfunction "(ADC5)PA5_32") (pintype "bidirectional"))
      (node (ref "X1") (pin "12") (pinfunction "P$1_12") (pintype "bidirectional"))
    )
    (net (code "37") (name "Net-(IC1-(ADC6)PA6)") (class "Default")
      (node (ref "IC1") (pin "31") (pinfunction "(ADC6)PA6_31") (pintype "bidirectional"))
      (node (ref "X1") (pin "13") (pinfunction "P$1_13") (pintype "bidirectional"))
    )
    (net (code "38") (name "Net-(IC1-(ADC7)PA7)") (class "Default")
      (node (ref "IC1") (pin "30") (pinfunction "(ADC7)PA7_30") (pintype "bidirectional"))
      (node (ref "X1") (pin "14") (pinfunction "P$1_14") (pintype "bidirectional"))
    )
    (net (code "39") (name "Net-(IC1-(ICP)PD6)") (class "Default")
      (node (ref "C6") (pin "1") (pinfunction "1_1") (pintype "passive"))
      (node (ref "IC1") (pin "15") (pinfunction "(ICP)PD6_15") (pintype "bidirectional"))
      (node (ref "R14") (pin "1") (pinfunction "1_1") (pintype "passive"))
    )
    (net (code "40") (name "Net-(IC1-(INT0)PD2)") (class "Default")
      (node (ref "C4") (pin "1") (pinfunction "1_1") (pintype "passive"))
      (node (ref "IC1") (pin "11") (pinfunction "(INT0)PD2_11") (pintype "bidirectional"))
      (node (ref "R12") (pin "1") (pinfunction "1_1") (pintype "passive"))
    )
    (net (code "41") (name "Net-(IC1-(INT1)PD3)") (class "Default")
      (node (ref "C5") (pin "1") (pinfunction "1_1") (pintype "passive"))
      (node (ref "IC1") (pin "12") (pinfunction "(INT1)PD3_12") (pintype "bidirectional"))
      (node (ref "R13") (pin "1") (pinfunction "1_1") (pintype "passive"))
    )
    (net (code "42") (name "Net-(IC1-AREF)") (class "Default")
      (node (ref "C8") (pin "1") (pinfunction "1_1") (pintype "passive"))
      (node (ref "IC1") (pin "29") (pinfunction "AREF_29") (pintype "power_in"))
    )
    (net (code "43") (name "Net-(IC1-AVCC)") (class "Default")
      (node (ref "BEAD_A") (pin "1") (pinfunction "1_1") (pintype "passive"))
      (node (ref "IC1") (pin "27") (pinfunction "AVCC_27") (pintype "power_in"))
    )
    (net (code "44") (name "Net-(IC1-XTAL1)") (class "Default")
      (node (ref "C3") (pin "1") (pinfunction "1_1") (pintype "passive"))
      (node (ref "IC1") (pin "8") (pinfunction "XTAL1_8") (pintype "bidirectional"))
      (node (ref "Q1") (pin "1") (pinfunction "1_1") (pintype "passive"))
    )
    (net (code "45") (name "Net-(IC1-XTAL2)") (class "Default")
      (node (ref "C2") (pin "1") (pinfunction "1_1") (pintype "passive"))
      (node (ref "IC1") (pin "7") (pinfunction "XTAL2_7") (pintype "bidirectional"))
      (node (ref "Q1") (pin "2") (pinfunction "2_2") (pintype "passive"))
    )
    (net (code "46") (name "Net-(IC4-OUT1)") (class "Default")
      (node (ref "IC4") (pin "6") (pinfunction "OUT1_6") (pintype "bidirectional"))
      (node (ref "IC4") (pin "7") (pinfunction "OUT2_7") (pintype "bidirectional"))
      (node (ref "R_G_W") (pin "1") (pinfunction "1_1") (pintype "passive"))
    )
    (net (code "47") (name "Net-(IC6-OUT1)") (class "Default")
      (node (ref "IC6") (pin "6") (pinfunction "OUT1_6") (pintype "bidirectional"))
      (node (ref "IC6") (pin "7") (pinfunction "OUT2_7") (pintype "bidirectional"))
      (node (ref "R_G_B") (pin "1") (pinfunction "1_1") (pintype "passive"))
    )
    (net (code "48") (name "Net-(IC7-OUT1)") (class "Default")
      (node (ref "IC7") (pin "6") (pinfunction "OUT1_6") (pintype "bidirectional"))
      (node (ref "IC7") (pin "7") (pinfunction "OUT2_7") (pintype "bidirectional"))
      (node (ref "R_G_G") (pin "1") (pinfunction "1_1") (pintype "passive"))
    )
    (net (code "49") (name "Net-(IC8-OUT1)") (class "Default")
      (node (ref "IC8") (pin "6") (pinfunction "OUT1_6") (pintype "bidirectional"))
      (node (ref "IC8") (pin "7") (pinfunction "OUT2_7") (pintype "bidirectional"))
      (node (ref "R_G_R") (pin "1") (pinfunction "1_1") (pintype "passive"))
    )
    (net (code "50") (name "Net-(LED4-PadA)") (class "Default")
      (node (ref "LED4") (pin "A") (pinfunction "A_A") (pintype "passive"))
      (node (ref "R4") (pin "1") (pinfunction "1_1") (pintype "passive"))
    )
    (net (code "51") (name "Net-(SW1-1)") (class "Default")
      (node (ref "R15") (pin "2") (pinfunction "2_2") (pintype "passive"))
      (node (ref "SW1") (pin "P$1") (pinfunction "1_P$1") (pintype "bidirectional"))
    )
    (net (code "52") (name "Net-(X1G-P$1)") (class "Default")
      (node (ref "R17") (pin "1") (pinfunction "1_1") (pintype "passive"))
      (node (ref "X1") (pin "15") (pinfunction "P$1_15") (pintype "bidirectional"))
    )
    (net (code "53") (name "Net-(X1J-P$1)") (class "Default")
      (node (ref "R18") (pin "1") (pinfunction "1_1") (pintype "passive"))
      (node (ref "R19") (pin "2") (pinfunction "2_2") (pintype "passive"))
      (node (ref "X1") (pin "3") (pinfunction "P$1_3") (pintype "bidirectional"))
    )
    (net (code "54") (name "PWM_B") (class "Default")
      (node (ref "IC1") (pin "16") (pinfunction "(OC2)PD7_16") (pintype "bidirectional"))
      (node (ref "IC6") (pin "2") (pinfunction "IN_2") (pintype "bidirectional"))
    )
    (net (code "55") (name "PWM_G") (class "Default")
      (node (ref "IC1") (pin "14") (pinfunction "(OC1A)PD5_14") (pintype "bidirectional"))
      (node (ref "IC7") (pin "2") (pinfunction "IN_2") (pintype "bidirectional"))
    )
    (net (code "56") (name "PWM_R") (class "Default")
      (node (ref "IC1") (pin "13") (pinfunction "(OC1B)PD4_13") (pintype "bidirectional"))
      (node (ref "IC8") (pin "2") (pinfunction "IN_2") (pintype "bidirectional"))
    )
    (net (code "57") (name "PWM_W") (class "Default")
      (node (ref "IC1") (pin "43") (pinfunction "(AIN1/OC0)PB3_43") (pintype "bidirectional"))
      (node (ref "IC4") (pin "2") (pinfunction "IN_2") (pintype "bidirectional"))
    )
    (net (code "58") (name "RXD_AVR") (class "Default")
      (node (ref "IC1") (pin "9") (pinfunction "(RXD)PD0_9") (pintype "bidirectional"))
      (node (ref "IC5") (pin "1") (pinfunction "RO_1") (pintype "bidirectional"))
    )
    (net (code "59") (name "SCK") (class "Default")
      (node (ref "CON5") (pin "3") (pinfunction "P$3_3") (pintype "bidirectional"))
      (node (ref "IC1") (pin "3") (pinfunction "(SCK)PB7_3") (pintype "bidirectional"))
    )
    (net (code "60") (name "TXD_AVR") (class "Default")
      (node (ref "IC1") (pin "10") (pinfunction "(TXD)PD1_10") (pintype "bidirectional"))
      (node (ref "IC5") (pin "4") (pinfunction "DI_4") (pintype "bidirectional"))
    )
    (net (code "61") (name "V+") (class "Default")
      (node (ref "C14") (pin "1") (pinfunction "1_1") (pintype "passive"))
      (node (ref "C15") (pin "1") (pinfunction "1_1") (pintype "passive"))
      (node (ref "C16") (pin "+") (pinfunction "+_+") (pintype "passive"))
      (node (ref "C17") (pin "+") (pinfunction "+_+") (pintype "passive"))
      (node (ref "C20") (pin "+") (pinfunction "+_+") (pintype "passive"))
      (node (ref "C21") (pin "+") (pinfunction "+_+") (pintype "passive"))
      (node (ref "C22") (pin "+") (pinfunction "+_+") (pintype "passive"))
      (node (ref "C23") (pin "+") (pinfunction "+_+") (pintype "passive"))
      (node (ref "C24") (pin "1") (pinfunction "1_1") (pintype "passive"))
      (node (ref "C25") (pin "1") (pinfunction "1_1") (pintype "passive"))
      (node (ref "C26") (pin "1") (pinfunction "1_1") (pintype "passive"))
      (node (ref "C27") (pin "1") (pinfunction "1_1") (pintype "passive"))
      (node (ref "C28") (pin "1") (pinfunction "1_1") (pintype "passive"))
      (node (ref "C29") (pin "1") (pinfunction "1_1") (pintype "passive"))
      (node (ref "C30") (pin "1") (pinfunction "1_1") (pintype "passive"))
      (node (ref "C31") (pin "1") (pinfunction "1_1") (pintype "passive"))
      (node (ref "C32") (pin "1") (pinfunction "1_1") (pintype "passive"))
      (node (ref "C40") (pin "1") (pinfunction "1_1") (pintype "passive"))
      (node (ref "CON3") (pin "5.1") (pinfunction "5.1_5.1") (pintype "bidirectional"))
      (node (ref "CON3") (pin "5.2") (pinfunction "5.2_5.2") (pintype "bidirectional"))
      (node (ref "CON3") (pin "6.1") (pinfunction "6.1_6.1") (pintype "bidirectional"))
      (node (ref "CON3") (pin "6.2") (pinfunction "6.2_6.2") (pintype "bidirectional"))
      (node (ref "CON4") (pin "1.1") (pinfunction "P$1_1.1") (pintype "bidirectional"))
      (node (ref "CON4") (pin "1.2") (pinfunction "P$2_1.2") (pintype "bidirectional"))
      (node (ref "CON4") (pin "2.1") (pinfunction "P$3_2.1") (pintype "bidirectional"))
      (node (ref "CON4") (pin "2.2") (pinfunction "P$4_2.2") (pintype "bidirectional"))
      (node (ref "DB") (pin "K") (pinfunction "K_K") (pintype "bidirectional"))
      (node (ref "DG") (pin "K") (pinfunction "K_K") (pintype "bidirectional"))
      (node (ref "DR") (pin "K") (pinfunction "K_K") (pintype "bidirectional"))
      (node (ref "DW") (pin "K") (pinfunction "K_K") (pintype "bidirectional"))
      (node (ref "IC4") (pin "1") (pinfunction "VS1_1") (pintype "bidirectional"))
      (node (ref "IC4") (pin "8") (pinfunction "VS2_8") (pintype "bidirectional"))
      (node (ref "IC6") (pin "1") (pinfunction "VS1_1") (pintype "bidirectional"))
      (node (ref "IC6") (pin "8") (pinfunction "VS2_8") (pintype "bidirectional"))
      (node (ref "IC7") (pin "1") (pinfunction "VS1_1") (pintype "bidirectional"))
      (node (ref "IC7") (pin "8") (pinfunction "VS2_8") (pintype "bidirectional"))
      (node (ref "IC8") (pin "1") (pinfunction "VS1_1") (pintype "bidirectional"))
      (node (ref "IC8") (pin "8") (pinfunction "VS2_8") (pintype "bidirectional"))
      (node (ref "REG1") (pin "G") (pinfunction "IN_G") (pintype "bidirectional"))
    )
    (net (code "62") (name "VCC") (class "Default")
      (node (ref "BEAD_A") (pin "2") (pinfunction "2_2") (pintype "passive"))
      (node (ref "C10") (pin "1") (pinfunction "1_1") (pintype "passive"))
      (node (ref "C37") (pin "1") (pinfunction "1_1") (pintype "passive"))
      (node (ref "C38") (pin "1") (pinfunction "1_1") (pintype "passive"))
      (node (ref "C39") (pin "1") (pinfunction "1_1") (pintype "passive"))
      (node (ref "C41") (pin "1") (pinfunction "1_1") (pintype "passive"))
      (node (ref "C7") (pin "1") (pinfunction "1_1") (pintype "passive"))
      (node (ref "CON5") (pin "2") (pinfunction "P$2_2") (pintype "bidirectional"))
      (node (ref "D2") (pin "C") (pinfunction "C_C") (pintype "passive"))
      (node (ref "IC1") (pin "17") (pinfunction "VCC1_17") (pintype "power_in"))
      (node (ref "IC1") (pin "38") (pinfunction "VCC2_38") (pintype "power_in"))
      (node (ref "IC1") (pin "5") (pinfunction "VCC_5") (pintype "power_in"))
      (node (ref "IC5") (pin "8") (pinfunction "VCC_8") (pintype "bidirectional"))
      (node (ref "R1") (pin "2") (pinfunction "2_2") (pintype "passive"))
      (node (ref "R10") (pin "2") (pinfunction "2_2") (pintype "passive"))
      (node (ref "R11") (pin "2") (pinfunction "2_2") (pintype "passive"))
      (node (ref "R17") (pin "2") (pinfunction "2_2") (pintype "passive"))
      (node (ref "R18") (pin "2") (pinfunction "2_2") (pintype "passive"))
      (node (ref "R2") (pin "2") (pinfunction "2_2") (pintype "passive"))
      (node (ref "R3") (pin "2") (pinfunction "2_2") (pintype "passive"))
      (node (ref "R4") (pin "2") (pinfunction "2_2") (pintype "passive"))
      (node (ref "R5") (pin "2") (pinfunction "2_2") (pintype "passive"))
      (node (ref "R7") (pin "2") (pinfunction "2_2") (pintype "passive"))
      (node (ref "R8") (pin "2") (pinfunction "2_2") (pintype "passive"))
      (node (ref "R9") (pin "2") (pinfunction "2_2") (pintype "passive"))
      (node (ref "REG1") (pin "S") (pinfunction "OUT_S") (pintype "bidirectional"))
      (node (ref "X1") (pin "2") (pinfunction "P$1_2") (pintype "bidirectional"))
    )
    (net (code "63") (name "unconnected-(CON6-Pad1.3)") (class "Default")
      (node (ref "CON6") (pin "1.3") (pinfunction "1.3_1.3") (pintype "bidirectional"))
    )
    (net (code "64") (name "unconnected-(CON6-Pad1.4)") (class "Default")
      (node (ref "CON6") (pin "1.4") (pinfunction "1.4_1.4") (pintype "bidirectional"))
    )
    (net (code "65") (name "unconnected-(CON6-Pad1.5)") (class "Default")
      (node (ref "CON6") (pin "1.5") (pinfunction "1.5_1.5") (pintype "bidirectional"))
    )
    (net (code "66") (name "unconnected-(CON6-Pad1.6)") (class "Default")
      (node (ref "CON6") (pin "1.6") (pinfunction "1.6_1.6") (pintype "bidirectional"))
    )
    (net (code "67") (name "unconnected-(CON6-Pad2.3)") (class "Default")
      (node (ref "CON6") (pin "2.3") (pinfunction "2.3_2.3") (pintype "bidirectional"))
    )
    (net (code "68") (name "unconnected-(CON6-Pad2.4)") (class "Default")
      (node (ref "CON6") (pin "2.4") (pinfunction "2.4_2.4") (pintype "bidirectional"))
    )
    (net (code "69") (name "unconnected-(CON6-Pad2.5)") (class "Default")
      (node (ref "CON6") (pin "2.5") (pinfunction "2.5_2.5") (pintype "bidirectional"))
    )
    (net (code "70") (name "unconnected-(CON6-Pad2.6)") (class "Default")
      (node (ref "CON6") (pin "2.6") (pinfunction "2.6_2.6") (pintype "bidirectional"))
    )
    (net (code "71") (name "unconnected-(IC1-PC0(SCL)-Pad19)") (class "Default")
      (node (ref "IC1") (pin "19") (pinfunction "PC0(SCL)_19") (pintype "bidirectional"))
    )
    (net (code "72") (name "unconnected-(IC1-PC1(SDA)-Pad20)") (class "Default")
      (node (ref "IC1") (pin "20") (pinfunction "PC1(SDA)_20") (pintype "bidirectional"))
    )
    (net (code "73") (name "unconnected-(SW1-2-PadP$2)") (class "Default")
      (node (ref "SW1") (pin "P$2") (pinfunction "2_P$2") (pintype "bidirectional"))
    )
    (net (code "74") (name "{slash}RESET") (class "Default")
      (node (ref "C1") (pin "1") (pinfunction "1_1") (pintype "passive"))
      (node (ref "CON5") (pin "5") (pinfunction "P$5_5") (pintype "bidirectional"))
      (node (ref "D2") (pin "A") (pinfunction "A_A") (pintype "passive"))
      (node (ref "IC1") (pin "4") (pinfunction "RESET_4") (pintype "input"))
      (node (ref "R1") (pin "1") (pinfunction "1_1") (pintype "passive"))
    )
    (net (code "75") (name "{slash}RE_RS485") (class "Default")
      (node (ref "IC1") (pin "22") (pinfunction "(TMS)PC3_22") (pintype "bidirectional"))
      (node (ref "IC5") (pin "2") (pinfunction "/RE_2") (pintype "bidirectional"))
      (node (ref "R5") (pin "1") (pinfunction "1_1") (pintype "passive"))
    )
    (net (code "76") (name "{slash}SS") (class "Default")
      (node (ref "IC1") (pin "44") (pinfunction "(SS)PB4_44") (pintype "bidirectional"))
    )
  )
)
